# RS-485.net
KiCad netlist of a schematic drawn in Altium Designer
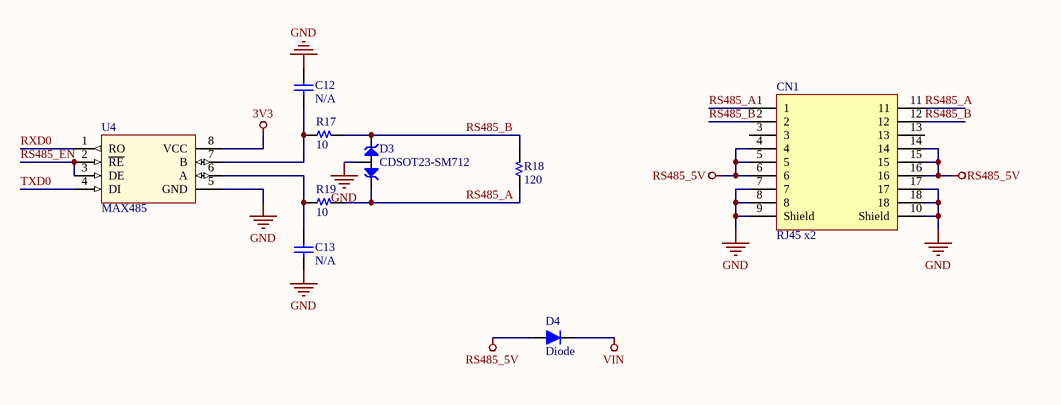
[diagram p0: RS-485.SchDoc]

(export (version "E")
  (design (tool "Eeschema 10.0.6"))
  (components
    (comp (ref "C12")
      (value "N/A")
      (footprint "C 0805")
      (description "Capacitor non-pol")
      (libsource (lib "chipfc_libs") (part "Capacitor NP"))
    )
    (comp (ref "C13")
      (value "N/A")
      (footprint "C 0805")
      (description "Capacitor non-pol")
      (libsource (lib "chipfc_libs") (part "Capacitor NP"))
    )
    (comp (ref "CN1")
      (value "RJ45 x2")
      (footprint "CONN/RJ45/x2")
      (description "Connector RJ45 X2")
      (libsource (lib "connectors") (part "CON RJ45 x2"))
    )
    (comp (ref "D3")
      (value "CDSOT23-SM712")
      (footprint "SOT-23")
      (description "TVS DIODE 7V/12V 14V/26V SOT23-3")
      (libsource (lib "chipfc_libs") (part "CDSOT23-SM712"))
    )
    (comp (ref "D4")
      (value "Diode")
      (footprint "SOD323")
      (description "Default Diode")
      (libsource (lib "chipfc_libs") (part "Diode"))
    )
    (comp (ref "R17")
      (value "10")
      (footprint "R 0805")
      (description "Resistor")
      (libsource (lib "chipfc_libs") (part "Resistor"))
    )
    (comp (ref "R18")
      (value "120")
      (footprint "R 0805")
      (description "Resistor")
      (libsource (lib "chipfc_libs") (part "Resistor"))
    )
    (comp (ref "R19")
      (value "10")
      (footprint "R 0805")
      (description "Resistor")
      (libsource (lib "chipfc_libs") (part "Resistor"))
    )
    (comp (ref "U4")
      (value "MAX485")
      (footprint "SOIC-8")
      (description "Low-Power, Slew-Rate-Limited  RS-485/RS-422 Transceivers")
      (libsource (lib "bs_libs") (part "MAX485"))
    )
  )
  (nets
    (net (code "1") (name "/RS485_A") (class "Default")
      (node (ref "CN1") (pin "1") (pinfunction "1_1") (pintype "passive"))
      (node (ref "CN1") (pin "11") (pinfunction "11_11") (pintype "passive"))
      (node (ref "D3") (pin "1") (pinfunction "IO1_1") (pintype "passive"))
      (node (ref "R18") (pin "1") (pinfunction "1_1") (pintype "passive"))
      (node (ref "R19") (pin "2") (pinfunction "2_2") (pintype "passive"))
    )
    (net (code "2") (name "/RS485_B") (class "Default")
      (node (ref "CN1") (pin "12") (pinfunction "12_12") (pintype "passive"))
      (node (ref "CN1") (pin "2") (pinfunction "2_2") (pintype "passive"))
      (node (ref "D3") (pin "2") (pinfunction "IO2_2") (pintype "passive"))
      (node (ref "R17") (pin "2") (pinfunction "2_2") (pintype "passive"))
      (node (ref "R18") (pin "2") (pinfunction "2_2") (pintype "passive"))
    )
    (net (code "3") (name "/RS485_EN") (class "Default")
      (node (ref "U4") (pin "2") (pinfunction "~{RE}_2") (pintype "input"))
      (node (ref "U4") (pin "3") (pinfunction "DE_3") (pintype "input"))
    )
    (net (code "4") (name "/RXD0") (class "Default")
      (node (ref "U4") (pin "1") (pinfunction "RO_1") (pintype "output"))
    )
    (net (code "5") (name "/TXD0") (class "Default")
      (node (ref "U4") (pin "4") (pinfunction "DI_4") (pintype "input"))
    )
    (net (code "6") (name "3V3") (class "Default")
      (node (ref "U4") (pin "8") (pinfunction "VCC_8") (pintype "passive"))
    )
    (net (code "7") (name "GND") (class "Default")
      (node (ref "C12") (pin "1") (pinfunction "1_1") (pintype "passive"))
      (node (ref "C13") (pin "2") (pinfunction "2_2") (pintype "passive"))
      (node (ref "CN1") (pin "10") (pinfunction "Shield_10") (pintype "passive"))
      (node (ref "CN1") (pin "17") (pinfunction "17_17") (pintype "passive"))
      (node (ref "CN1") (pin "18") (pinfunction "18_18") (pintype "passive"))
      (node (ref "CN1") (pin "7") (pinfunction "7_7") (pintype "passive"))
      (node (ref "CN1") (pin "8") (pinfunction "8_8") (pintype "passive"))
      (node (ref "CN1") (pin "9") (pinfunction "Shield_9") (pintype "passive"))
      (node (ref "D3") (pin "3") (pinfunction "COM_3") (pintype "passive"))
      (node (ref "U4") (pin "5") (pinfunction "GND_5") (pintype "passive"))
    )
    (net (code "8") (name "Net-(U4-A)") (class "Default")
      (node (ref "C13") (pin "1") (pinfunction "1_1") (pintype "passive"))
      (node (ref "R19") (pin "1") (pinfunction "1_1") (pintype "passive"))
      (node (ref "U4") (pin "6") (pinfunction "A_6") (pintype "bidirectional"))
    )
    (net (code "9") (name "Net-(U4-B)") (class "Default")
      (node (ref "C12") (pin "2") (pinfunction "2_2") (pintype "passive"))
      (node (ref "R17") (pin "1") (pinfunction "1_1") (pintype "passive"))
      (node (ref "U4") (pin "7") (pinfunction "B_7") (pintype "bidirectional"))
    )
    (net (code "10") (name "RS485_5V") (class "Default")
      (node (ref "CN1") (pin "14") (pinfunction "14_14") (pintype "passive"))
      (node (ref "CN1") (pin "15") (pinfunction "15_15") (pintype "passive"))
      (node (ref "CN1") (pin "16") (pinfunction "16_16") (pintype "passive"))
      (node (ref "CN1") (pin "4") (pinfunction "4_4") (pintype "passive"))
      (node (ref "CN1") (pin "5") (pinfunction "5_5") (pintype "passive"))
      (node (ref "CN1") (pin "6") (pinfunction "6_6") (pintype "passive"))
      (node (ref "D4") (pin "1") (pinfunction "A_1") (pintype "passive"))
    )
    (net (code "11") (name "VIN") (class "Default")
      (node (ref "D4") (pin "2") (pinfunction "K_2") (pintype "passive"))
    )
    (net (code "12") (name "unconnected-(CN1-Pad3)") (class "Default")
      (node (ref "CN1") (pin "3") (pinfunction "3_3") (pintype "passive"))
    )
    (net (code "13") (name "unconnected-(CN1-Pad13)") (class "Default")
      (node (ref "CN1") (pin "13") (pinfunction "13_13") (pintype "passive"))
    )
  )
)
